# max_plate.net
KiCad netlist of a schematic drawn in EAGLE
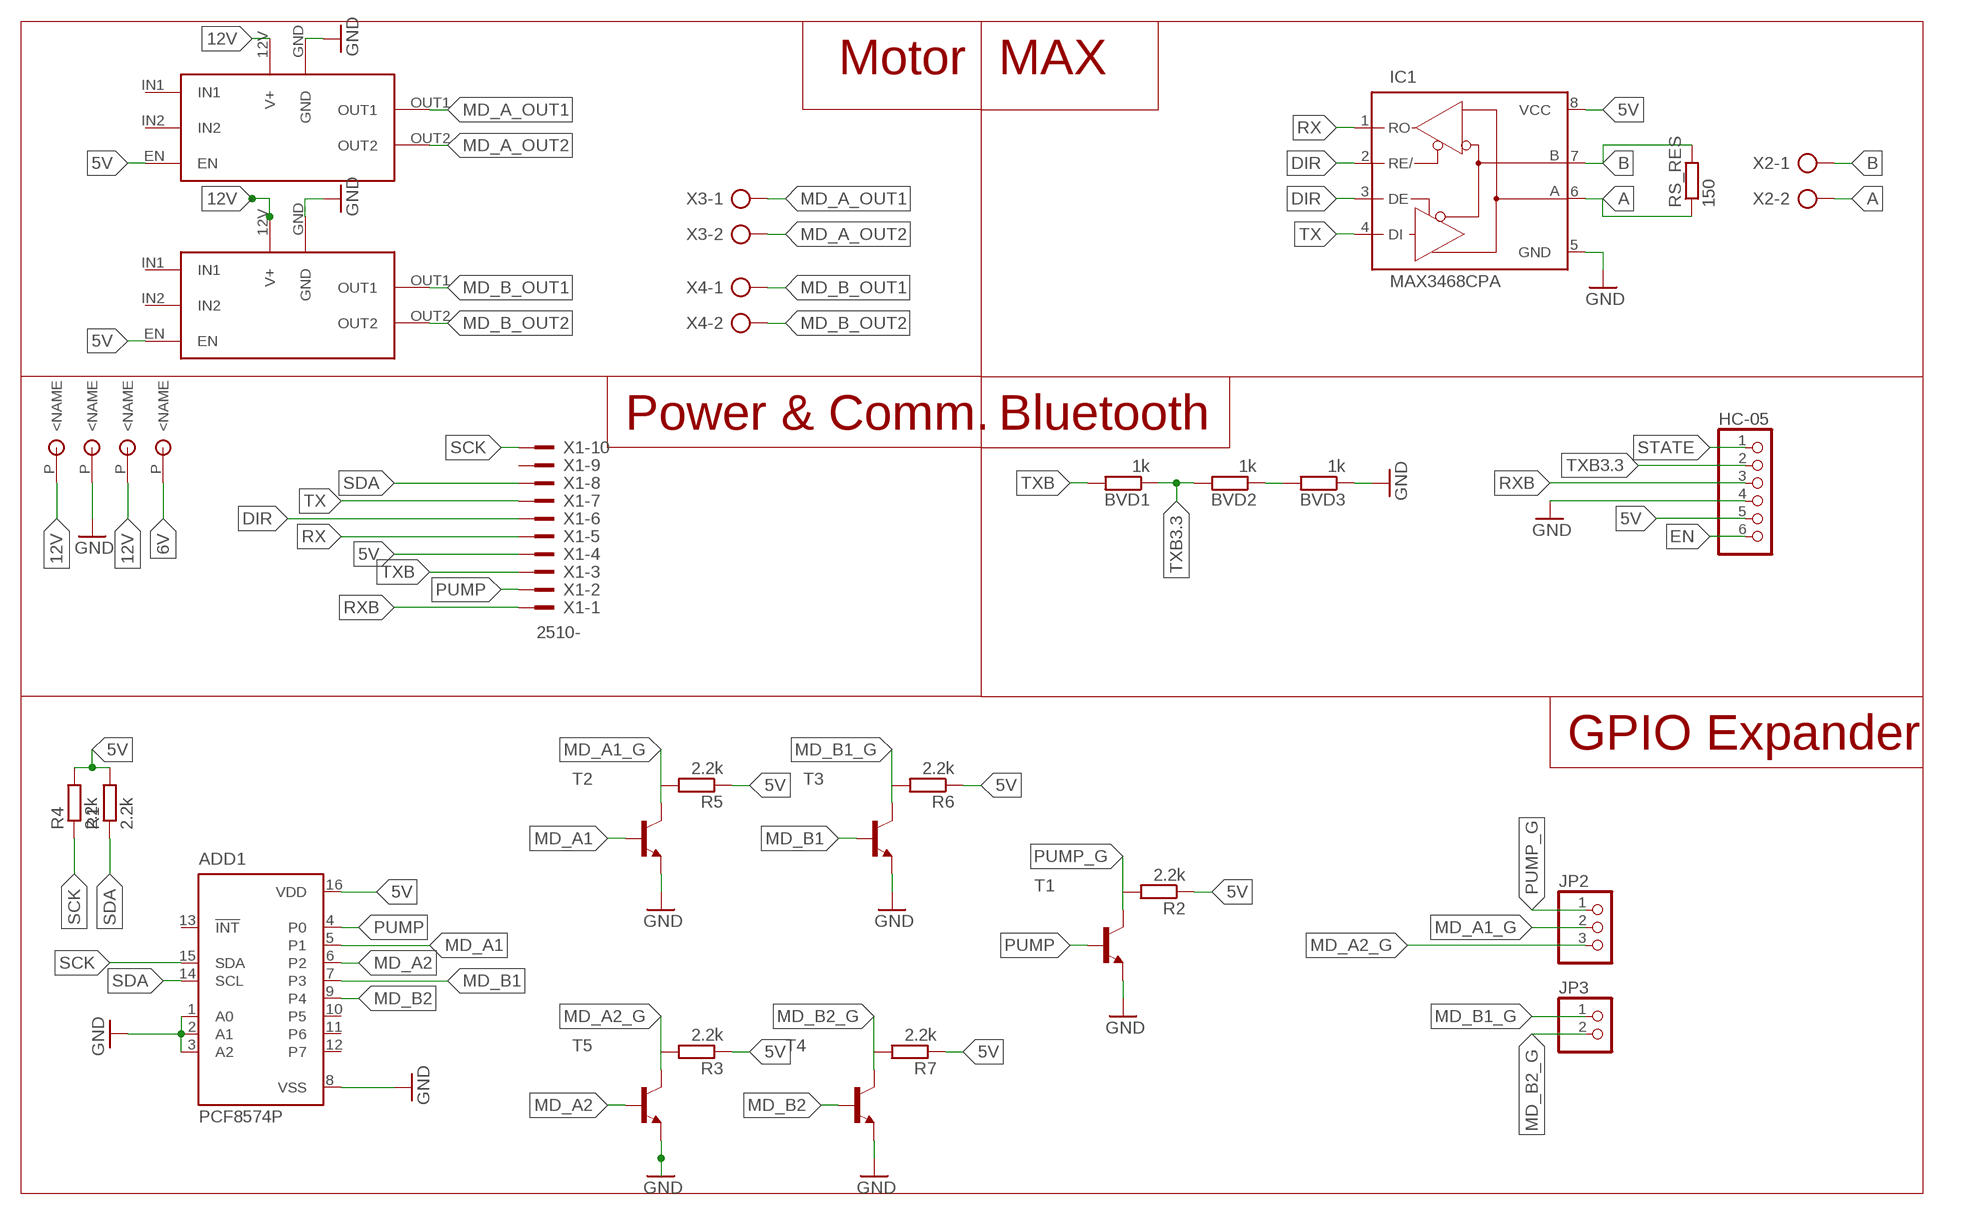
[diagram p0: schematic, sheet 1]

(export (version "E")
  (design (tool "Eeschema 10.0.6"))
  (components
    (comp (ref "ADD1")
      (value "PCF8574P")
      (footprint "eagle-import:DIL16")
      (fields (field (name "MPN") "PCF8574PN"))
      (libsource (lib "eagle-import") (part "PCF8574P"))
    )
    (comp (ref "BVD1")
      (value "1k")
      (footprint "eagle-import:0207_10")
      (libsource (lib "eagle-import") (part "R-EU_0207/10"))
    )
    (comp (ref "BVD2")
      (value "1k")
      (footprint "eagle-import:0207_10")
      (libsource (lib "eagle-import") (part "R-EU_0207/10"))
    )
    (comp (ref "BVD3")
      (value "1k")
      (footprint "eagle-import:0207_10")
      (libsource (lib "eagle-import") (part "R-EU_0207/10"))
    )
    (comp (ref "HC-05")
      (value "PINHD-1X6")
      (footprint "eagle-import:1X06")
      (libsource (lib "eagle-import") (part "PINHD-1X6"))
    )
    (comp (ref "IC1")
      (value "MAX3468CPA")
      (footprint "eagle-import:DIL08")
      (libsource (lib "eagle-import") (part "MAX34PA68C"))
    )
    (comp (ref "JP2")
      (value "PINHD-1X3")
      (footprint "eagle-import:1X03")
      (libsource (lib "eagle-import") (part "PINHD-1X3"))
    )
    (comp (ref "JP3")
      (value "PINHD-1X2")
      (footprint "eagle-import:1X02")
      (libsource (lib "eagle-import") (part "PINHD-1X2"))
    )
    (comp (ref "R1")
      (value "2.2k")
      (footprint "eagle-import:0207_10")
      (libsource (lib "eagle-import") (part "R-EU_0207/10"))
    )
    (comp (ref "R2")
      (value "2.2k")
      (footprint "eagle-import:0207_10")
      (libsource (lib "eagle-import") (part "R-EU_0207/10"))
    )
    (comp (ref "R3")
      (value "2.2k")
      (footprint "eagle-import:0207_10")
      (libsource (lib "eagle-import") (part "R-EU_0207/10"))
    )
    (comp (ref "R4")
      (value "2.2k")
      (footprint "eagle-import:0207_10")
      (libsource (lib "eagle-import") (part "R-EU_0207/10"))
    )
    (comp (ref "R5")
      (value "2.2k")
      (footprint "eagle-import:0207_10")
      (libsource (lib "eagle-import") (part "R-EU_0207/10"))
    )
    (comp (ref "R6")
      (value "2.2k")
      (footprint "eagle-import:0207_10")
      (libsource (lib "eagle-import") (part "R-EU_0207/10"))
    )
    (comp (ref "R7")
      (value "2.2k")
      (footprint "eagle-import:0207_10")
      (libsource (lib "eagle-import") (part "R-EU_0207/10"))
    )
    (comp (ref "RS_RES")
      (value "150")
      (footprint "eagle-import:0207_10")
      (libsource (lib "eagle-import") (part "R-EU_0207/10"))
    )
    (comp (ref "T1")
      (value "-NPN-TO92")
      (footprint "eagle-import:TO92")
      (libsource (lib "eagle-import") (part "-NPN-TO92"))
    )
    (comp (ref "T2")
      (value "-NPN-TO92")
      (footprint "eagle-import:TO92")
      (libsource (lib "eagle-import") (part "-NPN-TO92"))
    )
    (comp (ref "T3")
      (value "-NPN-TO92")
      (footprint "eagle-import:TO92")
      (libsource (lib "eagle-import") (part "-NPN-TO92"))
    )
    (comp (ref "T4")
      (value "-NPN-TO92")
      (footprint "eagle-import:TO92")
      (libsource (lib "eagle-import") (part "-NPN-TO92"))
    )
    (comp (ref "T5")
      (value "-NPN-TO92")
      (footprint "eagle-import:TO92")
      (libsource (lib "eagle-import") (part "-NPN-TO92"))
    )
    (comp (ref "U$1")
      (value "CU-SPACER")
      (footprint "eagle-import:CU-SPACER")
      (libsource (lib "eagle-import") (part "CU-SPACER"))
    )
    (comp (ref "U$2")
      (value "CU-SPACER")
      (footprint "eagle-import:CU-SPACER")
      (libsource (lib "eagle-import") (part "CU-SPACER"))
    )
    (comp (ref "U$3")
      (value "CU-SPACER")
      (footprint "eagle-import:CU-SPACER")
      (libsource (lib "eagle-import") (part "CU-SPACER"))
    )
    (comp (ref "U$4")
      (value "CU-SPACER")
      (footprint "eagle-import:CU-SPACER")
      (libsource (lib "eagle-import") (part "CU-SPACER"))
    )
    (comp (ref "U$5")
      (value "L6203-MODULE")
      (footprint "eagle-import:L6203-MODULE")
      (libsource (lib "eagle-import") (part "L6203-MODULE"))
    )
    (comp (ref "U$6")
      (value "L6203-MODULE")
      (footprint "eagle-import:L6203-MODULE")
      (libsource (lib "eagle-import") (part "L6203-MODULE"))
    )
    (comp (ref "X1")
      (value "2510-")
      (footprint "eagle-import:PAK100_2500-10")
      (fields (field (name "MF") "3M") (field (name "MPN") "2510-6002UB"))
      (libsource (lib "eagle-import") (part "2510-"))
    )
    (comp (ref "X2")
      (value "AK500/2")
      (footprint "eagle-import:AK500_2")
      (libsource (lib "eagle-import") (part "AK500/2"))
    )
    (comp (ref "X3")
      (value "AK500/2")
      (footprint "eagle-import:AK500_2")
      (libsource (lib "eagle-import") (part "AK500/2"))
    )
    (comp (ref "X4")
      (value "AK500/2")
      (footprint "eagle-import:AK500_2")
      (libsource (lib "eagle-import") (part "AK500/2"))
    )
  )
  (nets
    (net (code "1") (name "5V") (class "Default")
      (node (ref "ADD1") (pin "16") (pinfunction "VDD_16") (pintype "power_in"))
      (node (ref "HC-05") (pin "5") (pinfunction "5_5") (pintype "passive"))
      (node (ref "IC1") (pin "8") (pinfunction "VCC_8") (pintype "power_in"))
      (node (ref "R1") (pin "2") (pinfunction "2_2") (pintype "passive"))
      (node (ref "R2") (pin "1") (pinfunction "1_1") (pintype "passive"))
      (node (ref "R3") (pin "1") (pinfunction "1_1") (pintype "passive"))
      (node (ref "R4") (pin "2") (pinfunction "2_2") (pintype "passive"))
      (node (ref "R5") (pin "1") (pinfunction "1_1") (pintype "passive"))
      (node (ref "R6") (pin "1") (pinfunction "1_1") (pintype "passive"))
      (node (ref "R7") (pin "1") (pinfunction "1_1") (pintype "passive"))
      (node (ref "U$5") (pin "EN") (pinfunction "EN_EN") (pintype "bidirectional"))
      (node (ref "U$6") (pin "EN") (pinfunction "EN_EN") (pintype "bidirectional"))
      (node (ref "X1") (pin "4") (pinfunction "KL_4") (pintype "passive"))
    )
    (net (code "2") (name "6V") (class "Default")
      (node (ref "U$4") (pin "P") (pinfunction "<NAME_P") (pintype "bidirectional"))
    )
    (net (code "3") (name "12V") (class "Default")
      (node (ref "U$1") (pin "P") (pinfunction "<NAME_P") (pintype "bidirectional"))
      (node (ref "U$3") (pin "P") (pinfunction "<NAME_P") (pintype "bidirectional"))
      (node (ref "U$5") (pin "12V") (pinfunction "V+_12V") (pintype "bidirectional"))
      (node (ref "U$6") (pin "12V") (pinfunction "V+_12V") (pintype "bidirectional"))
    )
    (net (code "4") (name "A") (class "Default")
      (node (ref "IC1") (pin "6") (pinfunction "A_6") (pintype "passive"))
      (node (ref "RS_RES") (pin "1") (pinfunction "1_1") (pintype "passive"))
      (node (ref "X2") (pin "2") (pinfunction "KL_2") (pintype "passive"))
    )
    (net (code "5") (name "B") (class "Default")
      (node (ref "IC1") (pin "7") (pinfunction "B_7") (pintype "passive"))
      (node (ref "RS_RES") (pin "2") (pinfunction "2_2") (pintype "passive"))
      (node (ref "X2") (pin "1") (pinfunction "KL_1") (pintype "passive"))
    )
    (net (code "6") (name "DIR") (class "Default")
      (node (ref "IC1") (pin "2") (pinfunction "RE/_2") (pintype "input"))
      (node (ref "IC1") (pin "3") (pinfunction "DE_3") (pintype "input"))
      (node (ref "X1") (pin "6") (pinfunction "KL_6") (pintype "passive"))
    )
    (net (code "7") (name "EN") (class "Default")
      (node (ref "HC-05") (pin "6") (pinfunction "6_6") (pintype "passive"))
    )
    (net (code "8") (name "GND") (class "Default")
      (node (ref "ADD1") (pin "1") (pinfunction "A0_1") (pintype "input"))
      (node (ref "ADD1") (pin "2") (pinfunction "A1_2") (pintype "input"))
      (node (ref "ADD1") (pin "3") (pinfunction "A2_3") (pintype "input"))
      (node (ref "ADD1") (pin "8") (pinfunction "VSS_8") (pintype "power_in"))
      (node (ref "BVD3") (pin "1") (pinfunction "1_1") (pintype "passive"))
      (node (ref "HC-05") (pin "4") (pinfunction "4_4") (pintype "passive"))
      (node (ref "IC1") (pin "5") (pinfunction "GND_5") (pintype "power_in"))
      (node (ref "T1") (pin "1") (pinfunction "E_1") (pintype "passive"))
      (node (ref "T2") (pin "1") (pinfunction "E_1") (pintype "passive"))
      (node (ref "T3") (pin "1") (pinfunction "E_1") (pintype "passive"))
      (node (ref "T4") (pin "1") (pinfunction "E_1") (pintype "passive"))
      (node (ref "T5") (pin "1") (pinfunction "E_1") (pintype "passive"))
      (node (ref "U$2") (pin "P") (pinfunction "<NAME_P") (pintype "bidirectional"))
      (node (ref "U$5") (pin "GND") (pinfunction "GND_GND") (pintype "bidirectional"))
      (node (ref "U$6") (pin "GND") (pinfunction "GND_GND") (pintype "bidirectional"))
    )
    (net (code "9") (name "MD_A1") (class "Default")
      (node (ref "ADD1") (pin "5") (pinfunction "P1_5") (pintype "bidirectional"))
      (node (ref "T2") (pin "2") (pinfunction "B_2") (pintype "passive"))
    )
    (net (code "10") (name "MD_A1_G") (class "Default")
      (node (ref "JP2") (pin "2") (pinfunction "2_2") (pintype "passive"))
      (node (ref "R5") (pin "2") (pinfunction "2_2") (pintype "passive"))
      (node (ref "T2") (pin "3") (pinfunction "C_3") (pintype "passive"))
    )
    (net (code "11") (name "MD_A2") (class "Default")
      (node (ref "ADD1") (pin "6") (pinfunction "P2_6") (pintype "bidirectional"))
      (node (ref "T5") (pin "2") (pinfunction "B_2") (pintype "passive"))
    )
    (net (code "12") (name "MD_A2_G") (class "Default")
      (node (ref "JP2") (pin "3") (pinfunction "3_3") (pintype "passive"))
      (node (ref "R3") (pin "2") (pinfunction "2_2") (pintype "passive"))
      (node (ref "T5") (pin "3") (pinfunction "C_3") (pintype "passive"))
    )
    (net (code "13") (name "MD_A_OUT1") (class "Default")
      (node (ref "U$5") (pin "OUT1") (pinfunction "OUT1_OUT1") (pintype "bidirectional"))
      (node (ref "X3") (pin "1") (pinfunction "KL_1") (pintype "passive"))
    )
    (net (code "14") (name "MD_A_OUT2") (class "Default")
      (node (ref "U$5") (pin "OUT2") (pinfunction "OUT2_OUT2") (pintype "bidirectional"))
      (node (ref "X3") (pin "2") (pinfunction "KL_2") (pintype "passive"))
    )
    (net (code "15") (name "MD_B1") (class "Default")
      (node (ref "ADD1") (pin "7") (pinfunction "P3_7") (pintype "bidirectional"))
      (node (ref "T3") (pin "2") (pinfunction "B_2") (pintype "passive"))
    )
    (net (code "16") (name "MD_B1_G") (class "Default")
      (node (ref "JP3") (pin "1") (pinfunction "1_1") (pintype "passive"))
      (node (ref "R6") (pin "2") (pinfunction "2_2") (pintype "passive"))
      (node (ref "T3") (pin "3") (pinfunction "C_3") (pintype "passive"))
    )
    (net (code "17") (name "MD_B2") (class "Default")
      (node (ref "ADD1") (pin "9") (pinfunction "P4_9") (pintype "bidirectional"))
      (node (ref "T4") (pin "2") (pinfunction "B_2") (pintype "passive"))
    )
    (net (code "18") (name "MD_B2_G") (class "Default")
      (node (ref "JP3") (pin "2") (pinfunction "2_2") (pintype "passive"))
      (node (ref "R7") (pin "2") (pinfunction "2_2") (pintype "passive"))
      (node (ref "T4") (pin "3") (pinfunction "C_3") (pintype "passive"))
    )
    (net (code "19") (name "MD_B_OUT1") (class "Default")
      (node (ref "U$6") (pin "OUT1") (pinfunction "OUT1_OUT1") (pintype "bidirectional"))
      (node (ref "X4") (pin "1") (pinfunction "KL_1") (pintype "passive"))
    )
    (net (code "20") (name "MD_B_OUT2") (class "Default")
      (node (ref "U$6") (pin "OUT2") (pinfunction "OUT2_OUT2") (pintype "bidirectional"))
      (node (ref "X4") (pin "2") (pinfunction "KL_2") (pintype "passive"))
    )
    (net (code "21") (name "Net-(BVD2-Pad1)") (class "Default")
      (node (ref "BVD2") (pin "1") (pinfunction "1_1") (pintype "passive"))
      (node (ref "BVD3") (pin "2") (pinfunction "2_2") (pintype "passive"))
    )
    (net (code "22") (name "PUMP") (class "Default")
      (node (ref "ADD1") (pin "4") (pinfunction "P0_4") (pintype "bidirectional"))
      (node (ref "T1") (pin "2") (pinfunction "B_2") (pintype "passive"))
      (node (ref "X1") (pin "2") (pinfunction "KL_2") (pintype "passive"))
    )
    (net (code "23") (name "PUMP_G") (class "Default")
      (node (ref "JP2") (pin "1") (pinfunction "1_1") (pintype "passive"))
      (node (ref "R2") (pin "2") (pinfunction "2_2") (pintype "passive"))
      (node (ref "T1") (pin "3") (pinfunction "C_3") (pintype "passive"))
    )
    (net (code "24") (name "RX") (class "Default")
      (node (ref "IC1") (pin "1") (pinfunction "RO_1") (pintype "output"))
      (node (ref "X1") (pin "5") (pinfunction "KL_5") (pintype "passive"))
    )
    (net (code "25") (name "RXB") (class "Default")
      (node (ref "HC-05") (pin "3") (pinfunction "3_3") (pintype "passive"))
      (node (ref "X1") (pin "1") (pinfunction "KL_1") (pintype "passive"))
    )
    (net (code "26") (name "SCK") (class "Default")
      (node (ref "ADD1") (pin "15") (pinfunction "SDA_15") (pintype "bidirectional"))
      (node (ref "R4") (pin "1") (pinfunction "1_1") (pintype "passive"))
      (node (ref "X1") (pin "10") (pinfunction "KL_10") (pintype "passive"))
    )
    (net (code "27") (name "SDA") (class "Default")
      (node (ref "ADD1") (pin "14") (pinfunction "SCL_14") (pintype "input"))
      (node (ref "R1") (pin "1") (pinfunction "1_1") (pintype "passive"))
      (node (ref "X1") (pin "8") (pinfunction "KL_8") (pintype "passive"))
    )
    (net (code "28") (name "STATE") (class "Default")
      (node (ref "HC-05") (pin "1") (pinfunction "1_1") (pintype "passive"))
    )
    (net (code "29") (name "TX") (class "Default")
      (node (ref "IC1") (pin "4") (pinfunction "DI_4") (pintype "input"))
      (node (ref "X1") (pin "7") (pinfunction "KL_7") (pintype "passive"))
    )
    (net (code "30") (name "TXB") (class "Default")
      (node (ref "BVD1") (pin "2") (pinfunction "2_2") (pintype "passive"))
      (node (ref "X1") (pin "3") (pinfunction "KL_3") (pintype "passive"))
    )
    (net (code "31") (name "TXB3.3") (class "Default")
      (node (ref "BVD1") (pin "1") (pinfunction "1_1") (pintype "passive"))
      (node (ref "BVD2") (pin "2") (pinfunction "2_2") (pintype "passive"))
      (node (ref "HC-05") (pin "2") (pinfunction "2_2") (pintype "passive"))
    )
    (net (code "32") (name "unconnected-(ADD1-P5-Pad10)") (class "Default")
      (node (ref "ADD1") (pin "10") (pinfunction "P5_10") (pintype "bidirectional"))
    )
    (net (code "33") (name "unconnected-(ADD1-P6-Pad11)") (class "Default")
      (node (ref "ADD1") (pin "11") (pinfunction "P6_11") (pintype "bidirectional"))
    )
    (net (code "34") (name "unconnected-(ADD1-P7-Pad12)") (class "Default")
      (node (ref "ADD1") (pin "12") (pinfunction "P7_12") (pintype "bidirectional"))
    )
    (net (code "35") (name "unconnected-(ADD1-~{INT}-Pad13)") (class "Default")
      (node (ref "ADD1") (pin "13") (pinfunction "~{INT}_13") (pintype "output"))
    )
    (net (code "36") (name "unconnected-(U$5-PadIN1)") (class "Default")
      (node (ref "U$5") (pin "IN1") (pinfunction "IN1_IN1") (pintype "bidirectional"))
    )
    (net (code "37") (name "unconnected-(U$5-PadIN2)") (class "Default")
      (node (ref "U$5") (pin "IN2") (pinfunction "IN2_IN2") (pintype "bidirectional"))
    )
    (net (code "38") (name "unconnected-(U$6-PadIN1)") (class "Default")
      (node (ref "U$6") (pin "IN1") (pinfunction "IN1_IN1") (pintype "bidirectional"))
    )
    (net (code "39") (name "unconnected-(U$6-PadIN2)") (class "Default")
      (node (ref "U$6") (pin "IN2") (pinfunction "IN2_IN2") (pintype "bidirectional"))
    )
    (net (code "40") (name "unconnected-(X1J-KL-Pad9)") (class "Default")
      (node (ref "X1") (pin "9") (pinfunction "KL_9") (pintype "passive"))
    )
  )
)
